# Hardware_Tutorial_Controller_Board_Inter.net
KiCad netlist of a schematic drawn in Altium Designer
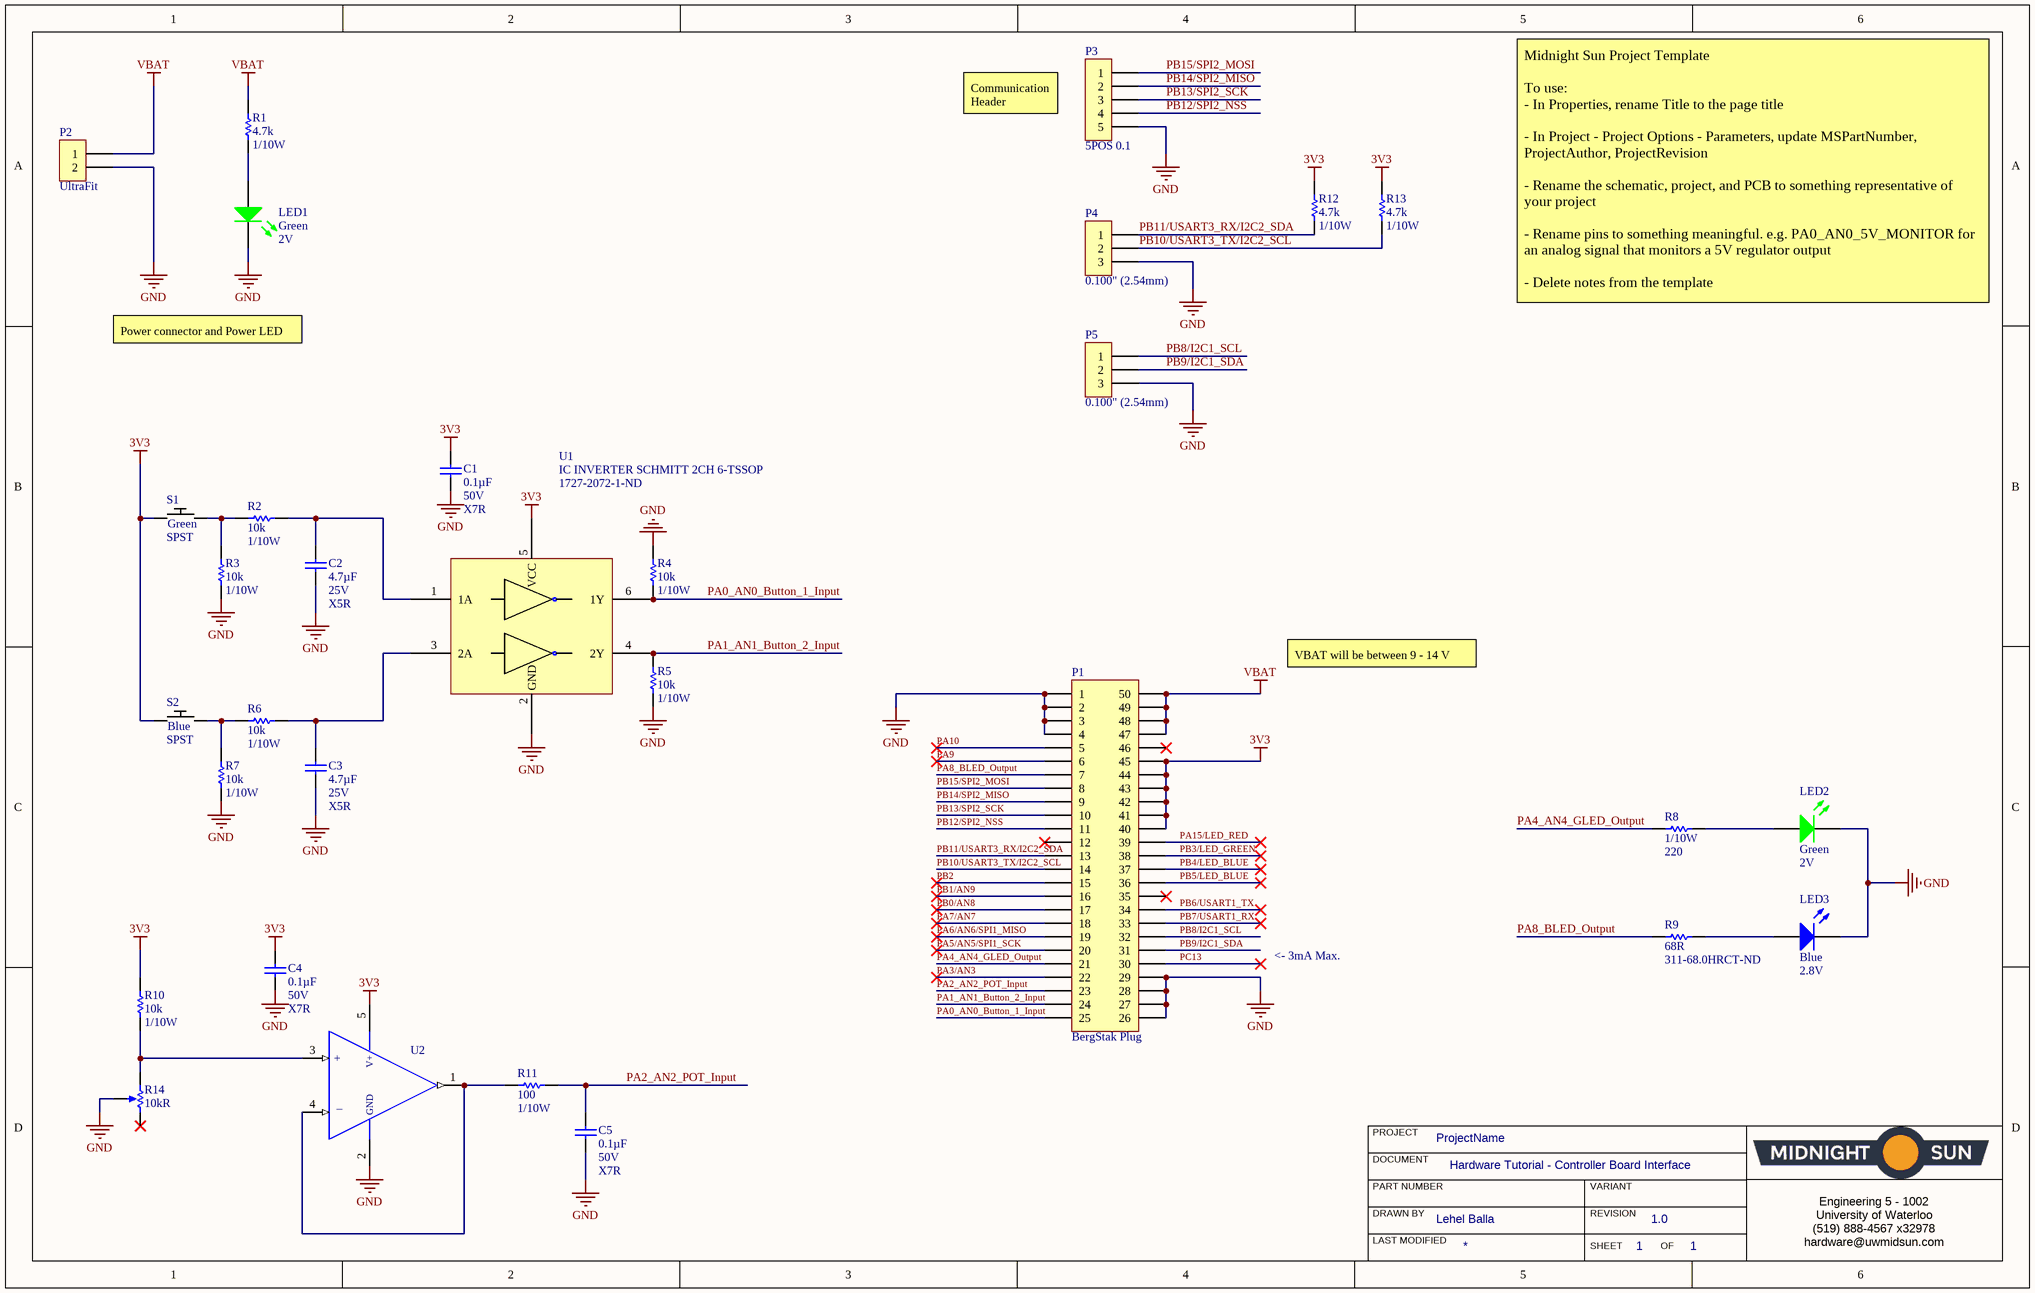
[diagram p0: Hardware_Tutorial_Controller_Board_Interface.SchDoc]

(export (version "E")
  (design (tool "Eeschema 10.0.6"))
  (components
    (comp (ref "C1")
      (value "CAP CER 0.1UF 50V 10% X7R 0603")
      (footprint "CAP, 0603")
      (description "0.10µF ±10% 50V Ceramic Capacitor X7R 0603 (1608 Metric)")
      (fields
        (field (name "TOLERANCE") "±10%")
        (field (name "CAPACITANCE") "0.1µF")
        (field (name "VOLTAGE") "50V")
        (field (name "TEMPERATURE COEFFICIENT") "X7R")
      )
      (libsource (lib "Schematic Diagrams") (part "CAP CER 0.1UF 50V 10% X7R 0603"))
    )
    (comp (ref "C2")
      (value "CAP CER 4.7UF 25V 10% X5R 0603")
      (footprint "CAP, 0603")
      (description "4.7µF ±10% 25V Ceramic Capacitor X5R 0603 (1608 Metric)")
      (fields
        (field (name "TOLERANCE") "±10%")
        (field (name "CAPACITANCE") "4.7µF")
        (field (name "VOLTAGE") "25V")
        (field (name "TEMPERATURE COEFFICIENT") "X5R")
      )
      (libsource (lib "Schematic Diagrams") (part "CAP CER 4.7UF 25V 10% X5R 0603"))
    )
    (comp (ref "C3")
      (value "CAP CER 4.7UF 25V 10% X5R 0603")
      (footprint "CAP, 0603")
      (description "4.7µF ±10% 25V Ceramic Capacitor X5R 0603 (1608 Metric)")
      (fields
        (field (name "TOLERANCE") "±10%")
        (field (name "CAPACITANCE") "4.7µF")
        (field (name "VOLTAGE") "25V")
        (field (name "TEMPERATURE COEFFICIENT") "X5R")
      )
      (libsource (lib "Schematic Diagrams") (part "CAP CER 4.7UF 25V 10% X5R 0603"))
    )
    (comp (ref "C4")
      (value "CAP CER 0.1UF 50V 10% X7R 0603")
      (footprint "CAP, 0603")
      (description "0.10µF ±10% 50V Ceramic Capacitor X7R 0603 (1608 Metric)")
      (fields
        (field (name "TOLERANCE") "±10%")
        (field (name "CAPACITANCE") "0.1µF")
        (field (name "VOLTAGE") "50V")
        (field (name "TEMPERATURE COEFFICIENT") "X7R")
      )
      (libsource (lib "Schematic Diagrams") (part "CAP CER 0.1UF 50V 10% X7R 0603"))
    )
    (comp (ref "C5")
      (value "CAP CER 0.1UF 50V 10% X7R 0603")
      (footprint "CAP, 0603")
      (description "0.10µF ±10% 50V Ceramic Capacitor X7R 0603 (1608 Metric)")
      (fields
        (field (name "TOLERANCE") "±10%")
        (field (name "CAPACITANCE") "0.1µF")
        (field (name "VOLTAGE") "50V")
        (field (name "TEMPERATURE COEFFICIENT") "X7R")
      )
      (libsource (lib "Schematic Diagrams") (part "CAP CER 0.1UF 50V 10% X7R 0603"))
    )
    (comp (ref "LED1")
      (value "LED GREEN CLEAR 2V 0603")
      (footprint "LED_0603")
      (description "Green 572nm LED Indication - Discrete 2V 0603 (1608 Metric)")
      (fields
        (field (name "MANUFACTURER") "Wurth Electronics Inc.")
        (field (name "MANUFACTURER PART NUMBER") "150060VS75000")
        (field (name "COLOR") "Green")
        (field (name "VOLTAGE - FORWARD (VF) (TYP)") "2V")
      )
      (libsource (lib "Schematic Diagrams") (part "LED GREEN CLEAR 2V 0603"))
    )
    (comp (ref "LED2")
      (value "LED GREEN CLEAR 2V 0603")
      (footprint "LED_0603")
      (description "Green 572nm LED Indication - Discrete 2V 0603 (1608 Metric)")
      (fields
        (field (name "MANUFACTURER") "Wurth Electronics Inc.")
        (field (name "MANUFACTURER PART NUMBER") "150060VS75000")
        (field (name "COLOR") "Green")
        (field (name "VOLTAGE - FORWARD (VF) (TYP)") "2V")
      )
      (libsource (lib "Schematic Diagrams") (part "LED GREEN CLEAR 2V 0603"))
    )
    (comp (ref "LED3")
      (value "LED BLUE CLEAR 2.8V 0603")
      (footprint "LED_0603")
      (description "Blue 470nm LED Indication - Discrete 2.8V 0603 (1608 Metric)")
      (fields (field (name "COLOR") "Blue") (field (name "VOLTAGE - FORWARD (VF) (TYP)") "2.8V"))
      (libsource (lib "Schematic Diagrams") (part "LED BLUE CLEAR 2.8V 0603"))
    )
    (comp (ref "P1")
      (value "CONN 50POS Bergstak Plug 0.02\"")
      (footprint "CONN, Bergstak 50 Pos Plug")
      (description "50 Position Connector Plug, Outer Shroud Contacts Surface Mount Gold")
      (fields (field (name "SERIES") "BergStak Plug"))
      (libsource (lib "Schematic Diagrams") (part "CONN 50POS Bergstak Plug 0.02{dblquote}"))
    )
    (comp (ref "P2")
      (value "CONN 2POS ULTRA-FIT 0.138\"")
      (footprint "CONN, 2POS ULTRA-FIT")
      (description "Connector Header Through Hole 2 position 0.138\" (3.50mm)")
      (fields
        (field (name "MANUFACTURER") "Molex")
        (field (name "MANUFACTURER PART NUMBER") "1722871102")
        (field (name "SERIES") "UltraFit")
      )
      (libsource (lib "Schematic Diagrams") (part "CONN 2POS ULTRA-FIT 0.138{dblquote}"))
    )
    (comp (ref "P3")
      (value "5POS 0.1")
      (footprint "CONN, 5POS HEADR 0.1\"")
      (description "5 Positions Header, Breakaway Connector 0.100\" (2.54mm) Through Hole Tin")
      (libsource (lib "Schematic Diagrams") (part "CONN 5POS HEADR MALE 0.1in"))
    )
    (comp (ref "P4")
      (value "CONN 3POS HEADR MALE 0.1\"")
      (footprint "CONN 3POS 0.100\" Header, 1 ROW")
      (description "3 Positions Header Connector 0.100\" (2.54mm) Through Hole Gold")
      (fields (field (name "VOLTAGE") "250V") (field (name "PITCH - MATING") "0.100\" (2.54mm)"))
      (libsource (lib "Schematic Diagrams") (part "CONN 3POS HEADR MALE 0.1{dblquote}"))
    )
    (comp (ref "P5")
      (value "CONN 3POS HEADR MALE 0.1\"")
      (footprint "CONN 3POS 0.100\" Header, 1 ROW")
      (description "3 Positions Header Connector 0.100\" (2.54mm) Through Hole Gold")
      (fields (field (name "VOLTAGE") "250V") (field (name "PITCH - MATING") "0.100\" (2.54mm)"))
      (libsource (lib "Schematic Diagrams") (part "CONN 3POS HEADR MALE 0.1{dblquote}"))
    )
    (comp (ref "R1")
      (value "RES 4.7K OHM 1% 1/10W 0603")
      (footprint "RES, 0603")
      (description "4.7k Ohm ±1% 0.1W, 1/10W Chip Resistor 0603 (1608 Metric) Moisture Resistant Thick Film")
      (fields
        (field (name "TOLERANCE") "±1%")
        (field (name "RESISTANCE (OHMS)") "4.7k")
        (field (name "POWER (WATTS)") "1/10W")
      )
      (libsource (lib "Schematic Diagrams") (part "RES 4.7K OHM 1% 1/10W 0603"))
    )
    (comp (ref "R2")
      (value "RES 10K OHM 1% 1/10W 0603")
      (footprint "RES, 0603")
      (description "RES SMD 10K OHM 1% 1/10W 0603")
      (fields
        (field (name "TOLERANCE") "±1%")
        (field (name "RESISTANCE") "10k")
        (field (name "POWER") "1/10W")
      )
      (libsource (lib "Schematic Diagrams") (part "RES 10K OHM 1% 1/10W 0603"))
    )
    (comp (ref "R3")
      (value "RES 10K OHM 1% 1/10W 0603")
      (footprint "RES, 0603")
      (description "RES SMD 10K OHM 1% 1/10W 0603")
      (fields
        (field (name "TOLERANCE") "±1%")
        (field (name "RESISTANCE") "10k")
        (field (name "POWER") "1/10W")
      )
      (libsource (lib "Schematic Diagrams") (part "RES 10K OHM 1% 1/10W 0603"))
    )
    (comp (ref "R4")
      (value "RES 10K OHM 1% 1/10W 0603")
      (footprint "RES, 0603")
      (description "RES SMD 10K OHM 1% 1/10W 0603")
      (fields
        (field (name "TOLERANCE") "±1%")
        (field (name "RESISTANCE") "10k")
        (field (name "POWER") "1/10W")
      )
      (libsource (lib "Schematic Diagrams") (part "RES 10K OHM 1% 1/10W 0603"))
    )
    (comp (ref "R5")
      (value "RES 10K OHM 1% 1/10W 0603")
      (footprint "RES, 0603")
      (description "RES SMD 10K OHM 1% 1/10W 0603")
      (fields
        (field (name "TOLERANCE") "±1%")
        (field (name "RESISTANCE") "10k")
        (field (name "POWER") "1/10W")
      )
      (libsource (lib "Schematic Diagrams") (part "RES 10K OHM 1% 1/10W 0603"))
    )
    (comp (ref "R6")
      (value "RES 10K OHM 1% 1/10W 0603")
      (footprint "RES, 0603")
      (description "RES SMD 10K OHM 1% 1/10W 0603")
      (fields
        (field (name "TOLERANCE") "±1%")
        (field (name "RESISTANCE") "10k")
        (field (name "POWER") "1/10W")
      )
      (libsource (lib "Schematic Diagrams") (part "RES 10K OHM 1% 1/10W 0603"))
    )
    (comp (ref "R7")
      (value "RES 10K OHM 1% 1/10W 0603")
      (footprint "RES, 0603")
      (description "RES SMD 10K OHM 1% 1/10W 0603")
      (fields
        (field (name "TOLERANCE") "±1%")
        (field (name "RESISTANCE") "10k")
        (field (name "POWER") "1/10W")
      )
      (libsource (lib "Schematic Diagrams") (part "RES 10K OHM 1% 1/10W 0603"))
    )
    (comp (ref "R8")
      (value "RES 220 OHM 1% 1/10W 0603")
      (footprint "RES, 0603")
      (description "220 Ohms ±1% 0.1W, 1/10W Chip Resistor 0603 (1608 Metric) Moisture Resistant Thick Film")
      (fields
        (field (name "MANUFACTURER") "Yageo")
        (field (name "MANUFACTURER PART NUMBER") "RC0603FR-07220RL")
        (field (name "POWER (WATTS)") "1/10W")
        (field (name "RESISTANCE") "220")
      )
      (libsource (lib "Schematic Diagrams") (part "RES 220 OHM 1% 1/10W 0603"))
    )
    (comp (ref "R9")
      (value "68R")
      (footprint "RES, 0603")
      (description "68 Ohm ±1% 0.1W, 1/10W Chip Resistor 0603 (1608 Metric) Moisture Resistant Thick Film")
      (fields
        (field (name "MANUFACTURER") "Yageo")
        (field (name "MANUFACTURER PART NUMBER") "RC0603FR-0768RL")
        (field (name "SUPPLIER PART NUMBER 1") "311-68.0HRCT-ND")
      )
      (libsource (lib "Schematic Diagrams") (part "RES 68 OHM 1% 1/10W 0603"))
    )
    (comp (ref "R10")
      (value "RES 10K OHM 1% 1/10W 0603")
      (footprint "RES, 0603")
      (description "RES SMD 10K OHM 1% 1/10W 0603")
      (fields
        (field (name "TOLERANCE") "±1%")
        (field (name "RESISTANCE") "10k")
        (field (name "POWER") "1/10W")
      )
      (libsource (lib "Schematic Diagrams") (part "RES 10K OHM 1% 1/10W 0603"))
    )
    (comp (ref "R11")
      (value "RES 100 OHM 1% 1/10W 0603")
      (footprint "RES, 0603")
      (description "100 Ohm ±1% 0.1W, 1/10W Chip Resistor 0603 (1608 Metric) Moisture Resistant Thick Film")
      (fields
        (field (name "TOLERANCE") "±1%")
        (field (name "RESISTANCE") "100")
        (field (name "POWER") "1/10W")
      )
      (libsource (lib "Schematic Diagrams") (part "RES 100 OHM 1% 1/10W 0603"))
    )
    (comp (ref "R12")
      (value "RES 4.7K OHM 1% 1/10W 0603")
      (footprint "RES, 0603")
      (description "4.7k Ohm ±1% 0.1W, 1/10W Chip Resistor 0603 (1608 Metric) Moisture Resistant Thick Film")
      (fields
        (field (name "TOLERANCE") "±1%")
        (field (name "RESISTANCE (OHMS)") "4.7k")
        (field (name "POWER (WATTS)") "1/10W")
      )
      (libsource (lib "Schematic Diagrams") (part "RES 4.7K OHM 1% 1/10W 0603"))
    )
    (comp (ref "R13")
      (value "RES 4.7K OHM 1% 1/10W 0603")
      (footprint "RES, 0603")
      (description "4.7k Ohm ±1% 0.1W, 1/10W Chip Resistor 0603 (1608 Metric) Moisture Resistant Thick Film")
      (fields
        (field (name "TOLERANCE") "±1%")
        (field (name "RESISTANCE (OHMS)") "4.7k")
        (field (name "POWER (WATTS)") "1/10W")
      )
      (libsource (lib "Schematic Diagrams") (part "RES 4.7K OHM 1% 1/10W 0603"))
    )
    (comp (ref "R14")
      (value "POT 10K OHM LINEAR THROUGH HOLE")
      (footprint "POT 10K OHM LINEAR THROUGH HOLE")
      (fields (field (name "TOLERANCE") "20%") (field (name "RESISTANCE") "10kR"))
      (libsource (lib "Schematic Diagrams") (part "POT 10K OHM LINEAR THROUGH HOLE"))
    )
    (comp (ref "S1")
      (value "SPST")
      (footprint "SW SPST D6 SERIES GREEN")
      (description "Pushbutton Switch SPST-NO Keyswitch Through Hole D6 Series Green")
      (fields (field (name "MANUFACTURER") "C&K") (field (name "MANUFACTURER PART NUMBER") "D6R50 F1 LFS"))
      (libsource (lib "Schematic Diagrams") (part "SW SPST-NO 0.1A 32V D6 Series Green"))
    )
    (comp (ref "S2")
      (value "SPST")
      (footprint "SW SPST D6 SERIES BLUE")
      (description "Pushbutton Switch SPST-NO Keyswitch Through Hole D6 Series Blue")
      (fields (field (name "MANUFACTURER") "C&K") (field (name "MANUFACTURER PART NUMBER") "D6R60 F1 LFS"))
      (libsource (lib "Schematic Diagrams") (part "SW SPST-NO 0.1A 32V D6 Series Blue"))
    )
    (comp (ref "U1")
      (value "IC INVERTER SCHMITT 2CH 6-TSSOP")
      (footprint "IC INVERTER SCHMITT 2CH 6-TSSOP")
      (description "Inverter IC 2 Channel Schmitt Trigger 6-TSSOP")
      (fields (field (name "SUPPLIER PART NUMBER 1") "1727-2072-1-ND"))
      (libsource (lib "Schematic Diagrams") (part "IC INVERTER SCHMITT 2CH 6-TSSOP"))
    )
    (comp (ref "U2")
      (value "IC OP AMP GEN PURPOSE RR 10MHZ SOT-23-5")
      (footprint "IC OP AMP GP RR 10MHZ SOT-23-5")
      (description "General Purpose Amplifier 1 Circuit Rail-to-Rail SOT-23-5")
      (libsource (lib "Schematic Diagrams") (part "IC OP AMP GEN PURPOSE RR 10MHZ SOT-23-5"))
    )
  )
  (nets
    (net (code "1") (name "/PA0_AN0_Button_1_Input") (class "Default")
      (node (ref "P1") (pin "25") (pinfunction "25_25") (pintype "passive"))
      (node (ref "R4") (pin "2") (pinfunction "2_2") (pintype "passive"))
      (node (ref "U1") (pin "6") (pinfunction "1Y_6") (pintype "passive"))
    )
    (net (code "2") (name "/PA1_AN1_Button_2_Input") (class "Default")
      (node (ref "P1") (pin "24") (pinfunction "24_24") (pintype "passive"))
      (node (ref "R5") (pin "1") (pinfunction "1_1") (pintype "passive"))
      (node (ref "U1") (pin "4") (pinfunction "2Y_4") (pintype "passive"))
    )
    (net (code "3") (name "/PA2_AN2_POT_Input") (class "Default")
      (node (ref "C5") (pin "1") (pinfunction "1_1") (pintype "passive"))
      (node (ref "P1") (pin "23") (pinfunction "23_23") (pintype "passive"))
      (node (ref "R11") (pin "2") (pinfunction "2_2") (pintype "passive"))
    )
    (net (code "4") (name "/PA3{slash}AN3") (class "Default")
      (node (ref "P1") (pin "22") (pinfunction "22_22") (pintype "passive+no_connect"))
    )
    (net (code "5") (name "/PA4_AN4_GLED_Output") (class "Default")
      (node (ref "P1") (pin "21") (pinfunction "21_21") (pintype "passive"))
      (node (ref "R8") (pin "1") (pinfunction "1_1") (pintype "passive"))
    )
    (net (code "6") (name "/PA5{slash}AN5{slash}SPI1_SCK") (class "Default")
      (node (ref "P1") (pin "20") (pinfunction "20_20") (pintype "passive+no_connect"))
    )
    (net (code "7") (name "/PA6{slash}AN6{slash}SPI1_MISO") (class "Default")
      (node (ref "P1") (pin "19") (pinfunction "19_19") (pintype "passive+no_connect"))
    )
    (net (code "8") (name "/PA7{slash}AN7") (class "Default")
      (node (ref "P1") (pin "18") (pinfunction "18_18") (pintype "passive+no_connect"))
    )
    (net (code "9") (name "/PA8_BLED_Output") (class "Default")
      (node (ref "P1") (pin "7") (pinfunction "7_7") (pintype "passive"))
      (node (ref "R9") (pin "1") (pinfunction "1_1") (pintype "passive"))
    )
    (net (code "10") (name "/PA9") (class "Default")
      (node (ref "P1") (pin "6") (pinfunction "6_6") (pintype "passive+no_connect"))
    )
    (net (code "11") (name "/PA10") (class "Default")
      (node (ref "P1") (pin "5") (pinfunction "5_5") (pintype "passive+no_connect"))
    )
    (net (code "12") (name "/PA15{slash}LED_RED") (class "Default")
      (node (ref "P1") (pin "39") (pinfunction "39_39") (pintype "passive+no_connect"))
    )
    (net (code "13") (name "/PB0{slash}AN8") (class "Default")
      (node (ref "P1") (pin "17") (pinfunction "17_17") (pintype "passive+no_connect"))
    )
    (net (code "14") (name "/PB1{slash}AN9") (class "Default")
      (node (ref "P1") (pin "16") (pinfunction "16_16") (pintype "passive+no_connect"))
    )
    (net (code "15") (name "/PB2") (class "Default")
      (node (ref "P1") (pin "15") (pinfunction "15_15") (pintype "passive+no_connect"))
    )
    (net (code "16") (name "/PB3{slash}LED_GREEN") (class "Default")
      (node (ref "P1") (pin "38") (pinfunction "38_38") (pintype "passive+no_connect"))
    )
    (net (code "17") (name "/PB4{slash}LED_BLUE") (class "Default")
      (node (ref "P1") (pin "37") (pinfunction "37_37") (pintype "passive+no_connect"))
    )
    (net (code "18") (name "/PB5{slash}LED_BLUE") (class "Default")
      (node (ref "P1") (pin "36") (pinfunction "36_36") (pintype "passive+no_connect"))
    )
    (net (code "19") (name "/PB6{slash}USART1_TX") (class "Default")
      (node (ref "P1") (pin "34") (pinfunction "34_34") (pintype "passive+no_connect"))
    )
    (net (code "20") (name "/PB7{slash}USART1_RX") (class "Default")
      (node (ref "P1") (pin "33") (pinfunction "33_33") (pintype "passive+no_connect"))
    )
    (net (code "21") (name "/PB8{slash}I2C1_SCL") (class "Default")
      (node (ref "P1") (pin "32") (pinfunction "32_32") (pintype "passive"))
      (node (ref "P5") (pin "1") (pinfunction "1_1") (pintype "passive"))
    )
    (net (code "22") (name "/PB9{slash}I2C1_SDA") (class "Default")
      (node (ref "P1") (pin "31") (pinfunction "31_31") (pintype "passive"))
      (node (ref "P5") (pin "2") (pinfunction "2_2") (pintype "passive"))
    )
    (net (code "23") (name "/PB10{slash}USART3_TX{slash}I2C2_SCL") (class "Default")
      (node (ref "P1") (pin "14") (pinfunction "14_14") (pintype "passive"))
      (node (ref "P4") (pin "2") (pinfunction "2_2") (pintype "passive"))
      (node (ref "R13") (pin "2") (pinfunction "2_2") (pintype "passive"))
    )
    (net (code "24") (name "/PB11{slash}USART3_RX{slash}I2C2_SDA") (class "Default")
      (node (ref "P1") (pin "13") (pinfunction "13_13") (pintype "passive"))
      (node (ref "P4") (pin "1") (pinfunction "1_1") (pintype "passive"))
      (node (ref "R12") (pin "2") (pinfunction "2_2") (pintype "passive"))
    )
    (net (code "25") (name "/PB12{slash}SPI2_NSS") (class "Default")
      (node (ref "P1") (pin "11") (pinfunction "11_11") (pintype "passive"))
      (node (ref "P3") (pin "4") (pinfunction "4_4") (pintype "passive"))
    )
    (net (code "26") (name "/PB13{slash}SPI2_SCK") (class "Default")
      (node (ref "P1") (pin "10") (pinfunction "10_10") (pintype "passive"))
      (node (ref "P3") (pin "3") (pinfunction "3_3") (pintype "passive"))
    )
    (net (code "27") (name "/PB14{slash}SPI2_MISO") (class "Default")
      (node (ref "P1") (pin "9") (pinfunction "9_9") (pintype "passive"))
      (node (ref "P3") (pin "2") (pinfunction "2_2") (pintype "passive"))
    )
    (net (code "28") (name "/PB15{slash}SPI2_MOSI") (class "Default")
      (node (ref "P1") (pin "8") (pinfunction "8_8") (pintype "passive"))
      (node (ref "P3") (pin "1") (pinfunction "1_1") (pintype "passive"))
    )
    (net (code "29") (name "/PC13") (class "Default")
      (node (ref "P1") (pin "30") (pinfunction "30_30") (pintype "passive+no_connect"))
    )
    (net (code "30") (name "3V3") (class "Default")
      (node (ref "C1") (pin "1") (pinfunction "1_1") (pintype "passive"))
      (node (ref "C4") (pin "1") (pinfunction "1_1") (pintype "passive"))
      (node (ref "P1") (pin "40") (pinfunction "40_40") (pintype "passive"))
      (node (ref "P1") (pin "41") (pinfunction "41_41") (pintype "passive"))
      (node (ref "P1") (pin "42") (pinfunction "42_42") (pintype "passive"))
      (node (ref "P1") (pin "43") (pinfunction "43_43") (pintype "passive"))
      (node (ref "P1") (pin "44") (pinfunction "44_44") (pintype "passive"))
      (node (ref "P1") (pin "45") (pinfunction "45_45") (pintype "passive"))
      (node (ref "R10") (pin "1") (pinfunction "1_1") (pintype "passive"))
      (node (ref "R12") (pin "1") (pinfunction "1_1") (pintype "passive"))
      (node (ref "R13") (pin "1") (pinfunction "1_1") (pintype "passive"))
      (node (ref "S1") (pin "1") (pinfunction "1_1") (pintype "passive"))
      (node (ref "S2") (pin "1") (pinfunction "1_1") (pintype "passive"))
      (node (ref "U1") (pin "5") (pinfunction "VCC_5") (pintype "passive"))
      (node (ref "U2") (pin "5") (pinfunction "VDD_5") (pintype "power_in"))
    )
    (net (code "31") (name "GND") (class "Default")
      (node (ref "C1") (pin "2") (pinfunction "2_2") (pintype "passive"))
      (node (ref "C2") (pin "2") (pinfunction "2_2") (pintype "passive"))
      (node (ref "C3") (pin "2") (pinfunction "2_2") (pintype "passive"))
      (node (ref "C4") (pin "2") (pinfunction "2_2") (pintype "passive"))
      (node (ref "C5") (pin "2") (pinfunction "2_2") (pintype "passive"))
      (node (ref "LED1") (pin "2") (pinfunction "K_2") (pintype "passive"))
      (node (ref "LED2") (pin "2") (pinfunction "K_2") (pintype "passive"))
      (node (ref "LED3") (pin "2") (pinfunction "K_2") (pintype "passive"))
      (node (ref "P1") (pin "1") (pinfunction "1_1") (pintype "passive"))
      (node (ref "P1") (pin "2") (pinfunction "2_2") (pintype "passive"))
      (node (ref "P1") (pin "26") (pinfunction "26_26") (pintype "passive"))
      (node (ref "P1") (pin "27") (pinfunction "27_27") (pintype "passive"))
      (node (ref "P1") (pin "28") (pinfunction "28_28") (pintype "passive"))
      (node (ref "P1") (pin "29") (pinfunction "29_29") (pintype "passive"))
      (node (ref "P1") (pin "3") (pinfunction "3_3") (pintype "passive"))
      (node (ref "P1") (pin "4") (pinfunction "4_4") (pintype "passive"))
      (node (ref "P2") (pin "2") (pinfunction "2_2") (pintype "passive"))
      (node (ref "P3") (pin "5") (pinfunction "5_5") (pintype "passive"))
      (node (ref "P4") (pin "3") (pinfunction "3_3") (pintype "passive"))
      (node (ref "P5") (pin "3") (pinfunction "3_3") (pintype "passive"))
      (node (ref "R14") (pin "2") (pinfunction "TAP_2") (pintype "passive"))
      (node (ref "R3") (pin "2") (pinfunction "2_2") (pintype "passive"))
      (node (ref "R4") (pin "1") (pinfunction "1_1") (pintype "passive"))
      (node (ref "R5") (pin "2") (pinfunction "2_2") (pintype "passive"))
      (node (ref "R7") (pin "2") (pinfunction "2_2") (pintype "passive"))
      (node (ref "U1") (pin "2") (pinfunction "GND_2") (pintype "passive"))
      (node (ref "U2") (pin "2") (pinfunction "VSS_2") (pintype "power_in"))
    )
    (net (code "32") (name "Net-(LED1-A)") (class "Default")
      (node (ref "LED1") (pin "1") (pinfunction "A_1") (pintype "passive"))
      (node (ref "R1") (pin "2") (pinfunction "2_2") (pintype "passive"))
    )
    (net (code "33") (name "Net-(LED2-A)") (class "Default")
      (node (ref "LED2") (pin "1") (pinfunction "A_1") (pintype "passive"))
      (node (ref "R8") (pin "2") (pinfunction "2_2") (pintype "passive"))
    )
    (net (code "34") (name "Net-(LED3-A)") (class "Default")
      (node (ref "LED3") (pin "1") (pinfunction "A_1") (pintype "passive"))
      (node (ref "R9") (pin "2") (pinfunction "2_2") (pintype "passive"))
    )
    (net (code "35") (name "Net-(R2-Pad2)") (class "Default")
      (node (ref "R2") (pin "2") (pinfunction "2_2") (pintype "passive"))
      (node (ref "R3") (pin "1") (pinfunction "1_1") (pintype "passive"))
      (node (ref "S1") (pin "2") (pinfunction "2_2") (pintype "passive"))
    )
    (net (code "36") (name "Net-(R6-Pad2)") (class "Default")
      (node (ref "R6") (pin "2") (pinfunction "2_2") (pintype "passive"))
      (node (ref "R7") (pin "1") (pinfunction "1_1") (pintype "passive"))
      (node (ref "S2") (pin "2") (pinfunction "2_2") (pintype "passive"))
    )
    (net (code "37") (name "Net-(R14-TOP)") (class "Default")
      (node (ref "R10") (pin "2") (pinfunction "2_2") (pintype "passive"))
      (node (ref "R14") (pin "1") (pinfunction "TOP_1") (pintype "passive"))
      (node (ref "U2") (pin "3") (pinfunction "+IN_3") (pintype "input"))
    )
    (net (code "38") (name "Net-(U1-1A)") (class "Default")
      (node (ref "C2") (pin "1") (pinfunction "1_1") (pintype "passive"))
      (node (ref "R2") (pin "1") (pinfunction "1_1") (pintype "passive"))
      (node (ref "U1") (pin "1") (pinfunction "1A_1") (pintype "passive"))
    )
    (net (code "39") (name "Net-(U1-2A)") (class "Default")
      (node (ref "C3") (pin "1") (pinfunction "1_1") (pintype "passive"))
      (node (ref "R6") (pin "1") (pinfunction "1_1") (pintype "passive"))
      (node (ref "U1") (pin "3") (pinfunction "2A_3") (pintype "passive"))
    )
    (net (code "40") (name "Net-(U2--IN)") (class "Default")
      (node (ref "R11") (pin "1") (pinfunction "1_1") (pintype "passive"))
      (node (ref "U2") (pin "1") (pinfunction "OUTPUT_1") (pintype "output"))
      (node (ref "U2") (pin "4") (pinfunction "-IN_4") (pintype "input"))
    )
    (net (code "41") (name "VBAT") (class "Default")
      (node (ref "P1") (pin "47") (pinfunction "47_47") (pintype "passive"))
      (node (ref "P1") (pin "48") (pinfunction "48_48") (pintype "passive"))
      (node (ref "P1") (pin "49") (pinfunction "49_49") (pintype "passive"))
      (node (ref "P1") (pin "50") (pinfunction "50_50") (pintype "passive"))
      (node (ref "P2") (pin "1") (pinfunction "1_1") (pintype "passive"))
      (node (ref "R1") (pin "1") (pinfunction "1_1") (pintype "passive"))
    )
    (net (code "42") (name "unconnected-(P1-Pad12)") (class "Default")
      (node (ref "P1") (pin "12") (pinfunction "12_12") (pintype "passive+no_connect"))
    )
    (net (code "43") (name "unconnected-(P1-Pad35)") (class "Default")
      (node (ref "P1") (pin "35") (pinfunction "35_35") (pintype "passive+no_connect"))
    )
    (net (code "44") (name "unconnected-(P1-Pad46)") (class "Default")
      (node (ref "P1") (pin "46") (pinfunction "46_46") (pintype "passive+no_connect"))
    )
    (net (code "45") (name "unconnected-(R14-BOT-Pad3)") (class "Default")
      (node (ref "R14") (pin "3") (pinfunction "BOT_3") (pintype "passive+no_connect"))
    )
  )
)
